# RFID.net
KiCad netlist of a schematic drawn in Altium Designer
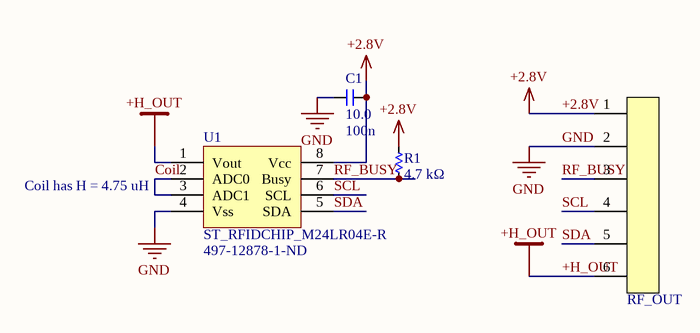
[diagram p0: RFID.SchDoc]

(export (version "E")
  (design (tool "Eeschema 10.0.6"))
  (components
    (comp (ref "C1")
      (value "399-3520-1-ND")
      (footprint "C0402")
      (fields
        (field (name "VOLTAGE") "10.0")
        (field (name "HUMAN_VALUE") "100n")
        (field (name "TOLERANCE") "10%")
      )
      (libsource (lib "sscp") (part "__template_cap"))
    )
    (comp (ref "R1")
      (value "__template_resistor")
      (footprint "R0805")
      (fields
        (field (name "RESISTANCE") "4.7 kΩ")
        (field (name "MANUFACTURER PART NUMBER") "RC0805FR-074K7L")
        (field (name "MANUFACTURER") "Yageo")
        (field (name "TOLERANCE") "±1%")
      )
      (libsource (lib "passives") (part "__template_resistor"))
    )
    (comp (ref "RF_OUT")
      (value "CONN HEADER 6POS RA SMT")
      (footprint "CONN_1X6_RA_SMT")
      (fields
        (field (name "MANUFACTURER") "3M")
        (field (name "MANUFACTURER PART NUMBER") "961106-5500-AR-PR")
      )
      (libsource (lib "SSI") (part "CONN_1x6_RA_SMT"))
    )
    (comp (ref "U1")
      (value "ST_RFIDCHIP_M24LR04E-R")
      (footprint "M24LR04E-R SO8N")
      (description "Dynamic NFC/RFID tag IC with 4-Kbit EEPROM,  energy harvesting, I²C bus and ISO 15693 RF interface")
      (fields
        (field (name "MANUFACTURER") "STMicroelectronics")
        (field (name "MANUFACTURER PART NUMBER") "M24LR04E-RMN6T/2")
        (field (name "SUPPLIER PART NUMBER 1") "497-12878-1-ND")
      )
      (libsource (lib "SSI") (part "ST_RFIDCHIP_M24LR04E-R"))
    )
  )
  (nets
    (net (code "1") (name "+2.8V") (class "Default")
      (node (ref "C1") (pin "2") (pintype "passive"))
      (node (ref "R1") (pin "2") (pintype "passive"))
      (node (ref "RF_OUT") (pin "1") (pinfunction "1_1") (pintype "passive"))
      (node (ref "U1") (pin "8") (pinfunction "Vcc_8") (pintype "power_in"))
    )
    (net (code "2") (name "+H_OUT") (class "Default")
      (node (ref "RF_OUT") (pin "6") (pinfunction "6_6") (pintype "passive"))
      (node (ref "U1") (pin "1") (pinfunction "Vout_1") (pintype "power_in"))
    )
    (net (code "3") (name "/Coil") (class "Default")
      (node (ref "U1") (pin "2") (pinfunction "ADC0_2") (pintype "power_in"))
      (node (ref "U1") (pin "3") (pinfunction "ADC1_3") (pintype "power_in"))
    )
    (net (code "4") (name "/RF_BUSY") (class "Default")
      (node (ref "R1") (pin "1") (pintype "passive"))
      (node (ref "RF_OUT") (pin "3") (pinfunction "3_3") (pintype "passive"))
      (node (ref "U1") (pin "7") (pinfunction "Busy_7") (pintype "power_in"))
    )
    (net (code "5") (name "/SCL") (class "Default")
      (node (ref "RF_OUT") (pin "4") (pinfunction "4_4") (pintype "passive"))
      (node (ref "U1") (pin "6") (pinfunction "SCL_6") (pintype "power_in"))
    )
    (net (code "6") (name "/SDA") (class "Default")
      (node (ref "RF_OUT") (pin "5") (pinfunction "5_5") (pintype "passive"))
      (node (ref "U1") (pin "5") (pinfunction "SDA_5") (pintype "power_in"))
    )
    (net (code "7") (name "GND") (class "Default")
      (node (ref "C1") (pin "1") (pintype "passive"))
      (node (ref "RF_OUT") (pin "2") (pinfunction "2_2") (pintype "passive"))
      (node (ref "U1") (pin "4") (pinfunction "Vss_4") (pintype "power_in"))
    )
  )
)
